# Temp_Sensor.net
KiCad netlist of a schematic drawn in Altium Designer
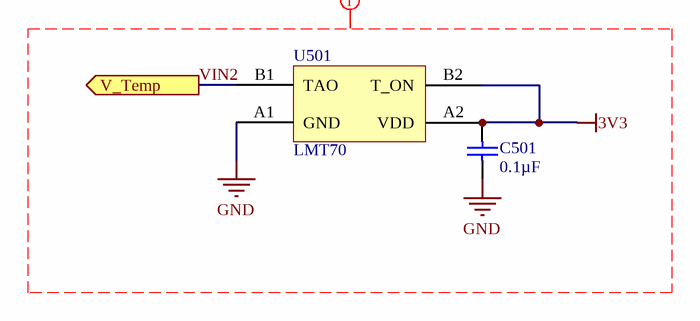
[diagram p0: Temp_Sensor.SchDoc]

(export (version "E")
  (design (tool "Eeschema 10.0.6"))
  (components
    (comp (ref "C501")
      (value "0.1µF")
      (footprint "TDK-CGA2B")
      (description "CAP CER 0.1UF 50V X7R 0402")
      (fields
        (field (name "PART NUMBER") "PC-TDK-02259")
        (field (name "MANUFACTURER PART NUMBER") "CGA2B3X7R1H104K050BB")
        (field (name "PUBLISHER") "AlbertaSat")
      )
      (libsource (lib "Database") (part "Cap"))
    )
    (comp (ref "U501")
      (value "LMT70")
      (footprint "TI-YFQ0004")
      (description "Temperature Sensor Analog, Local -55°C ~ 150°C 5.194mV/°C 4-DSBGA (0.81x0.81)")
      (fields (field (name "PART NUMBER") "70") (field (name "MANUFACTURER PART NUMBER") "LMT70YFQR"))
      (libsource (lib "Database") (part "LMT70"))
    )
  )
  (nets
    (net (code "1") (name "/VIN2") (class "Default")
      (node (ref "U501") (pin "B1") (pinfunction "TAO_B1") (pintype "passive"))
    )
    (net (code "2") (name "3V3") (class "Default")
      (node (ref "C501") (pin "2") (pinfunction "2_2") (pintype "passive"))
      (node (ref "U501") (pin "A2") (pinfunction "VDD_A2") (pintype "passive"))
      (node (ref "U501") (pin "B2") (pinfunction "T_ON_B2") (pintype "passive"))
    )
    (net (code "3") (name "GND") (class "Default")
      (node (ref "C501") (pin "1") (pinfunction "1_1") (pintype "passive"))
      (node (ref "U501") (pin "A1") (pinfunction "GND_A1") (pintype "passive"))
    )
  )
)
